# PowerCard.net
KiCad netlist of a schematic drawn in Altium Designer
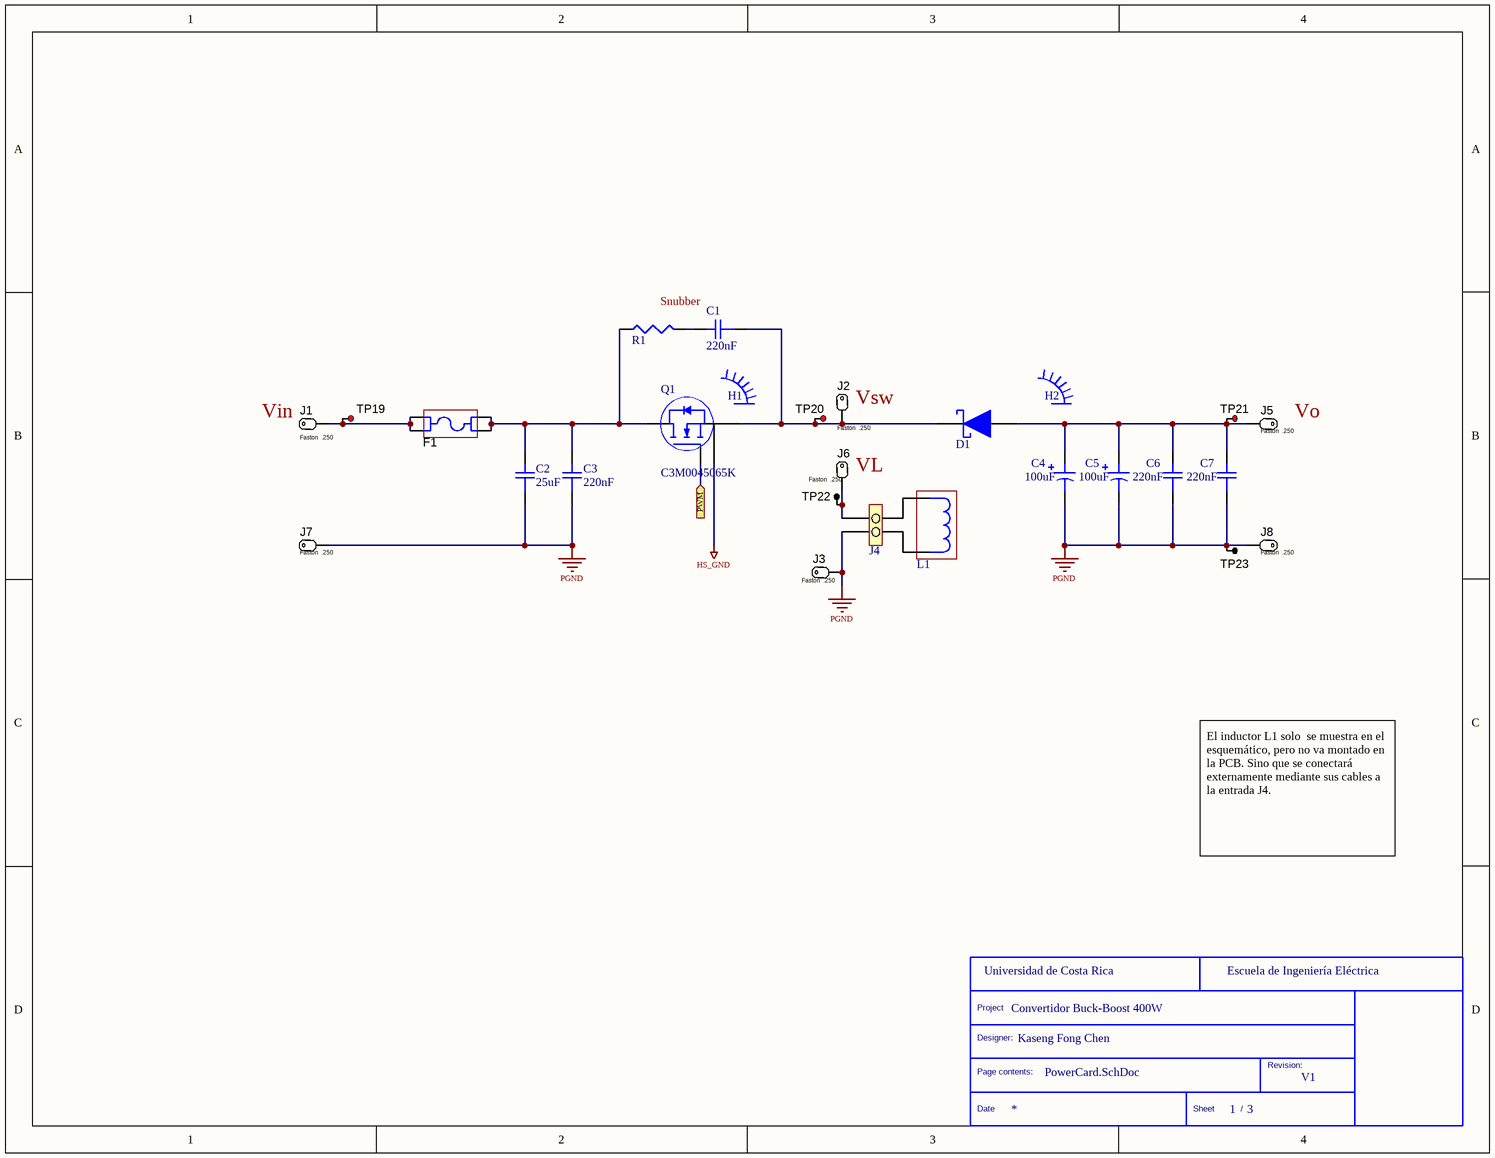
[diagram p0: PowerCard.SchDoc]

(export (version "E")
  (design (tool "Eeschema 10.0.6"))
  (components
    (comp (ref "C1")
      (value "220nF")
      (footprint "R75PI32204030J")
      (fields
        (field (name "MANUFACTURER") "KEMET")
        (field (name "MANUFACTURER PART NUMBER") "R75PI32204030J")
        (field (name "TOLERANCE") "5%")
      )
      (libsource (lib "KasengLIb") (part "R75PI32204030J"))
    )
    (comp (ref "C2")
      (value "25uF")
      (footprint "C4AQLBU5250A12K")
      (description "KEMET   C4AQLBU5250A12K.   CAP FILM 25UF 10% 500VDC RADIAL")
      (fields
        (field (name "MANUFACTURER") "KEMET")
        (field (name "MANUFACTURER PART NUMBER") "C4AQLBU5250A12K")
      )
      (libsource (lib "KasengLIb") (part "C4AQLBU5250A12K"))
    )
    (comp (ref "C3")
      (value "220nF")
      (footprint "R75PI32204030J")
      (fields
        (field (name "MANUFACTURER") "KEMET")
        (field (name "MANUFACTURER PART NUMBER") "R75PI32204030J")
        (field (name "TOLERANCE") "5%")
      )
      (libsource (lib "KasengLIb") (part "R75PI32204030J"))
    )
    (comp (ref "C4")
      (value "100uF")
      (footprint "CAP_MXC_22x35_RUB")
      (description "Cap Aluminum Lytic 100uF 475V 20% (22 X 35mm) Snap-In 10mm 880mA 2000h 105C")
      (fields
        (field (name "MANUFACTURER") "Rubycon")
        (field (name "MANUFACTURER PART NUMBER") "475MXH100MEFCSN22X35")
      )
      (libsource (lib "KasengLIb") (part "475MXH100MEFCSN22X35"))
    )
    (comp (ref "C5")
      (value "100uF")
      (footprint "CAP_MXC_22x35_RUB")
      (description "Cap Aluminum Lytic 100uF 475V 20% (22 X 35mm) Snap-In 10mm 880mA 2000h 105C")
      (fields
        (field (name "MANUFACTURER") "Rubycon")
        (field (name "MANUFACTURER PART NUMBER") "475MXH100MEFCSN22X35")
      )
      (libsource (lib "KasengLIb") (part "475MXH100MEFCSN22X35"))
    )
    (comp (ref "C6")
      (value "220nF")
      (footprint "R75PI32204030J")
      (fields
        (field (name "MANUFACTURER") "KEMET")
        (field (name "MANUFACTURER PART NUMBER") "R75PI32204030J")
        (field (name "TOLERANCE") "5%")
      )
      (libsource (lib "KasengLIb") (part "R75PI32204030J"))
    )
    (comp (ref "C7")
      (value "220nF")
      (footprint "R75PI32204030J")
      (fields
        (field (name "MANUFACTURER") "KEMET")
        (field (name "MANUFACTURER PART NUMBER") "R75PI32204030J")
        (field (name "TOLERANCE") "5%")
      )
      (libsource (lib "KasengLIb") (part "R75PI32204030J"))
    )
    (comp (ref "D1")
      (value "Schottky Diode")
      (footprint "C6D06065A")
      (description "Sic Schottky Diode, VRRM = 650V. IF= 6A")
      (fields
        (field (name "MANUFACTURER") "Cree Wolfspeed")
        (field (name "MANUFACTURER PART NUMBER") "C6D06065A")
      )
      (libsource (lib "kasengLib") (part "C6D06065A"))
    )
    (comp (ref "F1")
      (value "3101.0040")
      (footprint "SCHURTER_3101_0040")
      (description "Fuse Holder, 400 V, 16 A, TH")
      (fields
        (field (name "MANUFACTURER") "Schurter")
        (field (name "SYMBOLCREATOR") "a0799628")
        (field (name "PUBLISHER") "Texas Instruments")
      )
      (libsource (lib "KasengLIb") (part "3101.0040"))
    )
    (comp (ref "H1")
      (value "Disipador de 3.3.C/W")
      (footprint "HSINK_6399BG")
      (fields
        (field (name "MANUFACTURER") "Aavid Thermalloy")
        (field (name "MANUFACTURER PART NUMBER") "6399BG")
      )
      (libsource (lib "KasengLIb") (part "6399BG"))
    )
    (comp (ref "H2")
      (value "Disipador de 3.3.C/W")
      (footprint "HSINK_6399BG")
      (fields
        (field (name "MANUFACTURER") "Aavid Thermalloy")
        (field (name "MANUFACTURER PART NUMBER") "6399BG")
      )
      (libsource (lib "KasengLIb") (part "6399BG"))
    )
    (comp (ref "J1")
      (value "Faston  .250")
      (footprint "TE_62409-1")
      (description "Quick Disconnect Terminal M 15.8mm 7.5mm Tin Over Copper Automotive Bag")
      (fields
        (field (name "MANUFACTURER") "AMP - TE CONNECTIVITY")
        (field (name "MANUFACTURER PART NUMBER") "62409-1")
      )
      (libsource (lib "kasengLib") (part "62409-1"))
    )
    (comp (ref "J2")
      (value "Faston  .250")
      (footprint "TE_62409-1")
      (description "Quick Disconnect Terminal M 15.8mm 7.5mm Tin Over Copper Automotive Bag")
      (fields
        (field (name "MANUFACTURER") "AMP - TE CONNECTIVITY")
        (field (name "MANUFACTURER PART NUMBER") "62409-1")
      )
      (libsource (lib "kasengLib") (part "62409-1"))
    )
    (comp (ref "J3")
      (value "Faston  .250")
      (footprint "TE_62409-1")
      (description "Quick Disconnect Terminal M 15.8mm 7.5mm Tin Over Copper Automotive Bag")
      (fields
        (field (name "MANUFACTURER") "AMP - TE CONNECTIVITY")
        (field (name "MANUFACTURER PART NUMBER") "62409-1")
      )
      (libsource (lib "kasengLib") (part "62409-1"))
    )
    (comp (ref "J4")
      (value "2P Terminal,  12-20  AWG")
      (footprint "TE_8PCV-02-006")
      (description "Barrier Terminal Blocks VERTICAL RAISED 2P")
      (fields
        (field (name "MANUFACTURER") "TE Connectivity")
        (field (name "MANUFACTURER PART NUMBER") "8PCV-02-006")
      )
      (libsource (lib "KasengLIb") (part "8PCV-02-006"))
    )
    (comp (ref "J5")
      (value "Faston  .250")
      (footprint "TE_62409-1")
      (description "Quick Disconnect Terminal M 15.8mm 7.5mm Tin Over Copper Automotive Bag")
      (fields
        (field (name "MANUFACTURER") "AMP - TE CONNECTIVITY")
        (field (name "MANUFACTURER PART NUMBER") "62409-1")
      )
      (libsource (lib "kasengLib") (part "62409-1"))
    )
    (comp (ref "J6")
      (value "Faston  .250")
      (footprint "TE_62409-1")
      (description "Quick Disconnect Terminal M 15.8mm 7.5mm Tin Over Copper Automotive Bag")
      (fields
        (field (name "MANUFACTURER") "AMP - TE CONNECTIVITY")
        (field (name "MANUFACTURER PART NUMBER") "62409-1")
      )
      (libsource (lib "kasengLib") (part "62409-1"))
    )
    (comp (ref "J7")
      (value "Faston  .250")
      (footprint "TE_62409-1")
      (description "Quick Disconnect Terminal M 15.8mm 7.5mm Tin Over Copper Automotive Bag")
      (fields
        (field (name "MANUFACTURER") "AMP - TE CONNECTIVITY")
        (field (name "MANUFACTURER PART NUMBER") "62409-1")
      )
      (libsource (lib "kasengLib") (part "62409-1"))
    )
    (comp (ref "J8")
      (value "Faston  .250")
      (footprint "TE_62409-1")
      (description "Quick Disconnect Terminal M 15.8mm 7.5mm Tin Over Copper Automotive Bag")
      (fields
        (field (name "MANUFACTURER") "AMP - TE CONNECTIVITY")
        (field (name "MANUFACTURER PART NUMBER") "62409-1")
      )
      (libsource (lib "kasengLib") (part "62409-1"))
    )
    (comp (ref "L1")
      (value "Inductor is not mounted on PCB")
      (description "Fixed Inductors CHOKE")
      (fields
        (field (name "MANUFACTURER") "Hammond Manufacturing")
        (field (name "MANUFACTURER PART NUMBER") "195J10")
      )
      (libsource (lib "kasengLib") (part "195J10"))
    )
    (comp (ref "Q1")
      (value "C3M0045065K")
      (footprint "TO-247-4L_C3M0075120K_WFS")
      (description "Sic MOSFET 650V")
      (fields (field (name "MANUFACTURER") "Cree Wolfspeed"))
      (libsource (lib "KasengLIb") (part "C3M0045065K"))
    )
    (comp (ref "R1")
      (value "Wirewound, Snubber")
      (footprint "Wirewound Resistors 47 Ohms 7W 300PPM")
      (description "Wirewound Resistors 47 Ohms 7W 300PPM")
      (fields
        (field (name "MANUFACTURER") "TE Connectivity")
        (field (name "MANUFACTURER PART NUMBER") "SQMW747RJ")
      )
      (libsource (lib "kasengLib") (part "SQMW747RJ"))
    )
    (comp (ref "TP19")
      (value "5010")
      (footprint "Keystone5010")
      (description "Test Point, Multipurpose, Red, TH")
      (fields (field (name "MANUFACTURER") "Keystone") (field (name "PUBLISHER") "Texas Instruments"))
      (libsource (lib "kasengLib") (part "5010"))
    )
    (comp (ref "TP20")
      (value "5010")
      (footprint "Keystone5010")
      (description "Test Point, Multipurpose, Red, TH")
      (fields (field (name "MANUFACTURER") "Keystone") (field (name "PUBLISHER") "Texas Instruments"))
      (libsource (lib "kasengLib") (part "5010"))
    )
    (comp (ref "TP21")
      (value "5010")
      (footprint "Keystone5010")
      (description "Test Point, Multipurpose, Red, TH")
      (fields (field (name "MANUFACTURER") "Keystone") (field (name "PUBLISHER") "Texas Instruments"))
      (libsource (lib "kasengLib") (part "5010"))
    )
    (comp (ref "TP22")
      (value "5011")
      (footprint "Keystone5011")
      (description "Test Point, Multipurpose, Black, TH")
      (fields (field (name "MANUFACTURER") "Keystone") (field (name "PUBLISHER") "Texas Instruments"))
      (libsource (lib "kasengLib") (part "5011"))
    )
    (comp (ref "TP23")
      (value "5011")
      (footprint "Keystone5011")
      (description "Test Point, Multipurpose, Black, TH")
      (fields (field (name "MANUFACTURER") "Keystone") (field (name "PUBLISHER") "Texas Instruments"))
      (libsource (lib "kasengLib") (part "5011"))
    )
  )
  (nets
    (net (code "1") (name "/PWM") (class "Default")
      (node (ref "Q1") (pin "4") (pinfunction "G_4") (pintype "passive"))
    )
    (net (code "2") (name "HS_GND") (class "Default")
      (node (ref "Q1") (pin "3") (pinfunction "S_3") (pintype "passive"))
    )
    (net (code "3") (name "Net-(C1-Pad1)") (class "Default")
      (node (ref "C1") (pin "1") (pinfunction "1_1") (pintype "passive"))
      (node (ref "R1") (pin "2") (pinfunction "2_2") (pintype "passive"))
    )
    (net (code "4") (name "Net-(J1-P1)") (class "Default")
      (node (ref "F1") (pin "1") (pinfunction "1_1") (pintype "passive"))
      (node (ref "F1") (pin "2") (pinfunction "2_2") (pintype "passive"))
      (node (ref "J1") (pin "1") (pinfunction "P1_1") (pintype "passive"))
      (node (ref "TP19") (pin "1") (pinfunction "1_1") (pintype "passive"))
    )
    (net (code "5") (name "Net-(J2-P1)") (class "Default")
      (node (ref "C1") (pin "2") (pinfunction "2_2") (pintype "passive"))
      (node (ref "D1") (pin "1") (pinfunction "1_1") (pintype "passive"))
      (node (ref "J2") (pin "1") (pinfunction "P1_1") (pintype "passive"))
      (node (ref "Q1") (pin "2") (pinfunction "Power_Source_2") (pintype "passive"))
      (node (ref "TP20") (pin "1") (pinfunction "1_1") (pintype "passive"))
    )
    (net (code "6") (name "Net-(J5-P1)") (class "Default")
      (node (ref "C4") (pin "1") (pinfunction "1_1") (pintype "passive"))
      (node (ref "C5") (pin "1") (pinfunction "1_1") (pintype "passive"))
      (node (ref "C6") (pin "1") (pinfunction "1_1") (pintype "passive"))
      (node (ref "C7") (pin "1") (pinfunction "1_1") (pintype "passive"))
      (node (ref "D1") (pin "2") (pinfunction "2_2") (pintype "passive"))
      (node (ref "J5") (pin "1") (pinfunction "P1_1") (pintype "passive"))
      (node (ref "TP21") (pin "1") (pinfunction "1_1") (pintype "passive"))
    )
    (net (code "7") (name "Net-(J6-P1)") (class "Default")
      (node (ref "J4") (pin "2") (pinfunction "2_2") (pintype "passive"))
      (node (ref "J6") (pin "1") (pinfunction "P1_1") (pintype "passive"))
      (node (ref "TP22") (pin "1") (pinfunction "1_1") (pintype "passive"))
    )
    (net (code "8") (name "Net-(Q1-D)") (class "Default")
      (node (ref "C2") (pin "1") (pinfunction "1_1") (pintype "passive"))
      (node (ref "C3") (pin "1") (pinfunction "1_1") (pintype "passive"))
      (node (ref "F1") (pin "3") (pinfunction "3_3") (pintype "passive"))
      (node (ref "F1") (pin "4") (pinfunction "4_4") (pintype "passive"))
      (node (ref "Q1") (pin "1") (pinfunction "D_1") (pintype "passive"))
      (node (ref "R1") (pin "1") (pinfunction "1_1") (pintype "passive"))
    )
    (net (code "9") (name "PGND") (class "Default")
      (node (ref "C2") (pin "2") (pinfunction "2_2") (pintype "passive"))
      (node (ref "C3") (pin "2") (pinfunction "2_2") (pintype "passive"))
      (node (ref "C4") (pin "2") (pinfunction "2_2") (pintype "passive"))
      (node (ref "C5") (pin "2") (pinfunction "2_2") (pintype "passive"))
      (node (ref "C6") (pin "2") (pinfunction "2_2") (pintype "passive"))
      (node (ref "C7") (pin "2") (pinfunction "2_2") (pintype "passive"))
      (node (ref "J3") (pin "1") (pinfunction "P1_1") (pintype "passive"))
      (node (ref "J4") (pin "1") (pinfunction "1_1") (pintype "passive"))
      (node (ref "J7") (pin "1") (pinfunction "P1_1") (pintype "passive"))
      (node (ref "J8") (pin "1") (pinfunction "P1_1") (pintype "passive"))
      (node (ref "TP23") (pin "1") (pinfunction "1_1") (pintype "passive"))
    )
    (net (code "10") (name "unconnected-(L1-Pad1)") (class "Default")
      (node (ref "L1") (pin "1") (pinfunction "1_1") (pintype "passive"))
    )
    (net (code "11") (name "unconnected-(L1-Pad2)") (class "Default")
      (node (ref "L1") (pin "2") (pinfunction "2_2") (pintype "passive"))
    )
  )
)
